# SCH_Aansluitschema_Jao_2023-12-15.net
KiCad netlist of a schematic drawn in EasyEDA
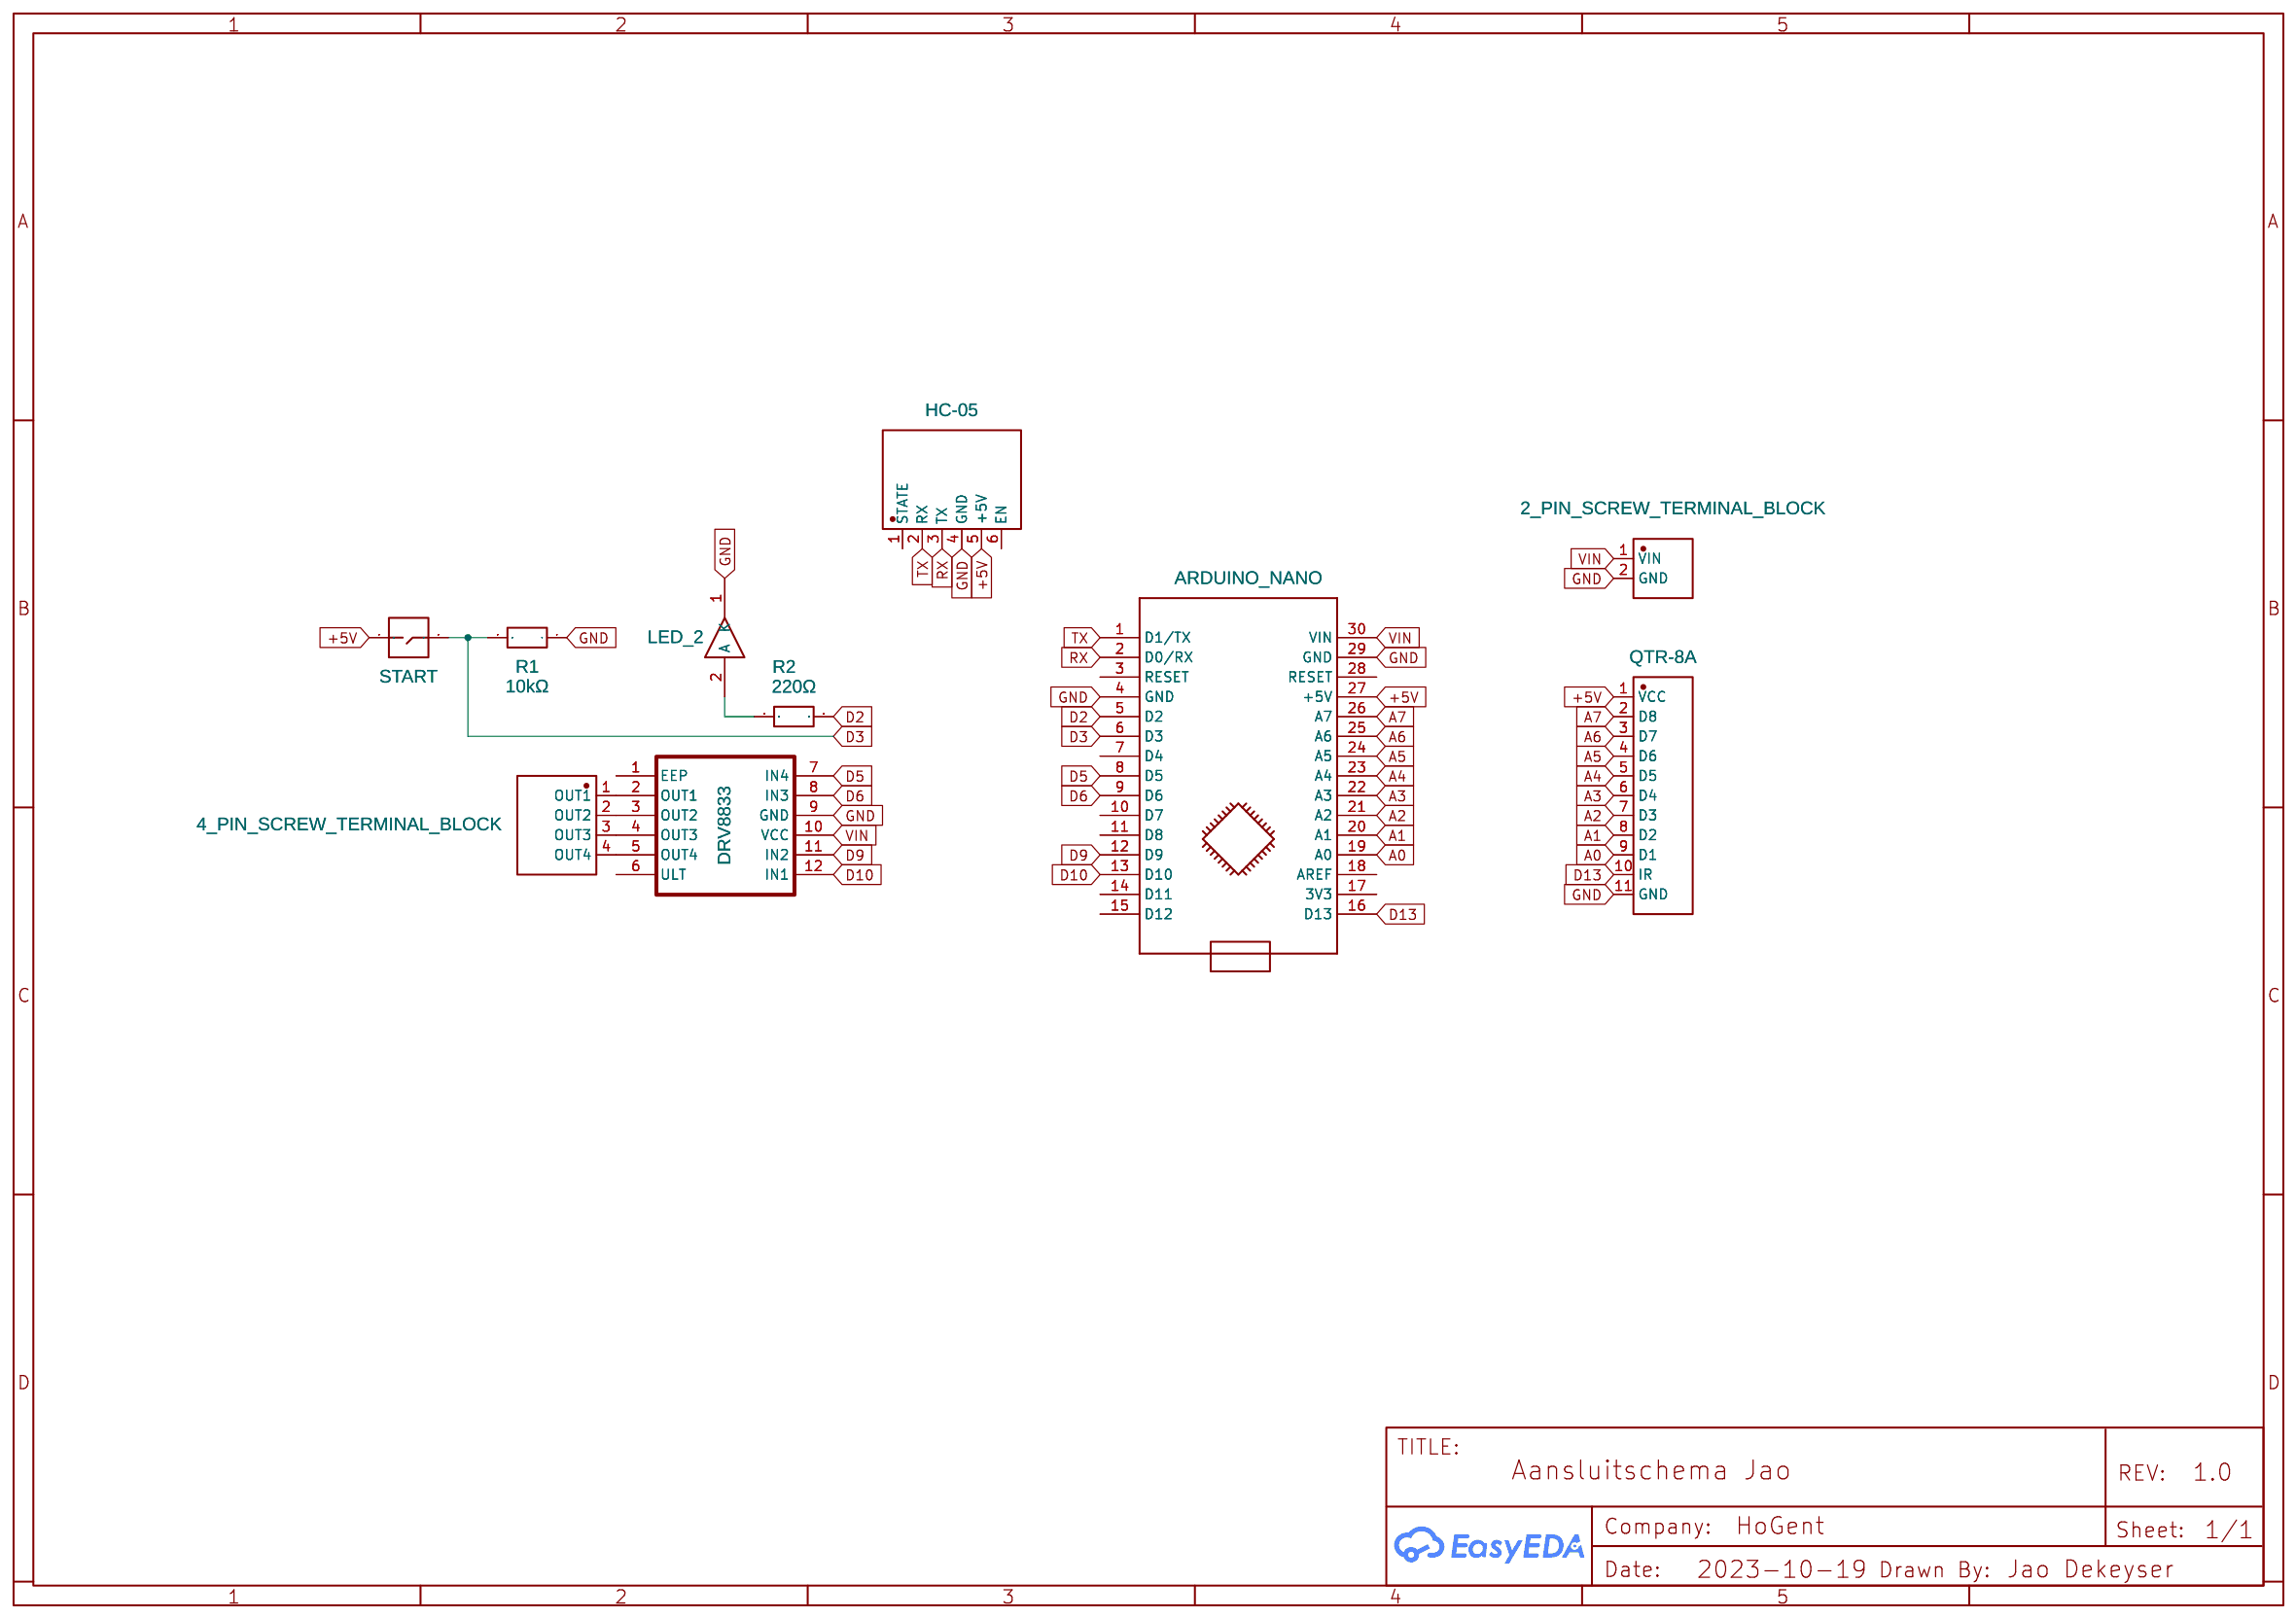
[diagram p0: schematic sheet]

(export (version "E")
  (design (tool "Eeschema 10.0.6"))
  (components
    (comp (ref "2_PIN_SCREW_TERMINAL_BLOCK")
      (value "2 Pin Screw Terminal Block Connector 2.54 mm")
      (libsource (lib "") (part "2 PIN SCREW TERMINAL BLOCK CONNECTOR 2.54 MM"))
    )
    (comp (ref "4_PIN_SCREW_TERMINAL_BLOCK")
      (value "4 PIN SCREW TERMINAL BLOCK CONNECTOR 2.54 MM")
      (libsource (lib "") (part "4 PIN SCREW TERMINAL BLOCK CONNECTOR 2.54 MM"))
    )
    (comp (ref "ARDUINO_NANO")
      (value "ARDUINO NANO CLOCK")
      (fields (field (name "Manufacturer Part") "Arduino-NANO"))
      (libsource (lib "") (part "ARDUINO NANO CLOCK"))
    )
    (comp (ref "DRV8833") (value "DRV8833") (libsource (lib "") (part "DRV8833 12PIN")))
    (comp (ref "HC-05") (value "HC-05") (libsource (lib "") (part "HC-05")))
    (comp (ref "LED_2") (value "led 5 mm") (libsource (lib "") (part "led 5 mm")))
    (comp (ref "QTR-8A") (value "QTR-8A") (libsource (lib "") (part "QTR-8A")))
    (comp (ref "R1")
      (value "10kΩ")
      (libsource (lib "") (part "AXIAL RESISTOR 220 OHM - TH_BD2.3-L6.0-P10.00-D0.4"))
    )
    (comp (ref "R2")
      (value "220Ω")
      (libsource (lib "") (part "AXIAL RESISTOR 220 OHM - TH_BD2.3-L6.0-P10.00-D0.4_1"))
    )
    (comp (ref "START") (value "start") (libsource (lib "") (part "Push Button")))
  )
  (nets
    (net (code "1") (name "+5V") (class "Default")
      (node (ref "ARDUINO_NANO") (pin "27") (pinfunction "+5V_27") (pintype "unspecified"))
      (node (ref "HC-05") (pin "5") (pinfunction "+5V_5") (pintype "unspecified"))
      (node (ref "QTR-8A") (pin "1") (pinfunction "VCC_1") (pintype "unspecified"))
      (node (ref "START") (pin "1") (pinfunction "1_1") (pintype "unspecified"))
    )
    (net (code "2") (name "A0") (class "Default")
      (node (ref "ARDUINO_NANO") (pin "19") (pinfunction "A0_19") (pintype "unspecified"))
      (node (ref "QTR-8A") (pin "9") (pinfunction "D1_9") (pintype "unspecified"))
    )
    (net (code "3") (name "A1") (class "Default")
      (node (ref "ARDUINO_NANO") (pin "20") (pinfunction "A1_20") (pintype "unspecified"))
      (node (ref "QTR-8A") (pin "8") (pinfunction "D2_8") (pintype "unspecified"))
    )
    (net (code "4") (name "A2") (class "Default")
      (node (ref "ARDUINO_NANO") (pin "21") (pinfunction "A2_21") (pintype "unspecified"))
      (node (ref "QTR-8A") (pin "7") (pinfunction "D3_7") (pintype "unspecified"))
    )
    (net (code "5") (name "A3") (class "Default")
      (node (ref "ARDUINO_NANO") (pin "22") (pinfunction "A3_22") (pintype "unspecified"))
      (node (ref "QTR-8A") (pin "6") (pinfunction "D4_6") (pintype "unspecified"))
    )
    (net (code "6") (name "A4") (class "Default")
      (node (ref "ARDUINO_NANO") (pin "23") (pinfunction "A4_23") (pintype "unspecified"))
      (node (ref "QTR-8A") (pin "5") (pinfunction "D5_5") (pintype "unspecified"))
    )
    (net (code "7") (name "A5") (class "Default")
      (node (ref "ARDUINO_NANO") (pin "24") (pinfunction "A5_24") (pintype "unspecified"))
      (node (ref "QTR-8A") (pin "4") (pinfunction "D6_4") (pintype "unspecified"))
    )
    (net (code "8") (name "A6") (class "Default")
      (node (ref "ARDUINO_NANO") (pin "25") (pinfunction "A6_25") (pintype "unspecified"))
      (node (ref "QTR-8A") (pin "3") (pinfunction "D7_3") (pintype "unspecified"))
    )
    (net (code "9") (name "A7") (class "Default")
      (node (ref "ARDUINO_NANO") (pin "26") (pinfunction "A7_26") (pintype "unspecified"))
      (node (ref "QTR-8A") (pin "2") (pinfunction "D8_2") (pintype "unspecified"))
    )
    (net (code "10") (name "D2") (class "Default")
      (node (ref "ARDUINO_NANO") (pin "5") (pinfunction "D2_5") (pintype "unspecified"))
      (node (ref "R2") (pin "2") (pinfunction "2_2") (pintype "unspecified"))
    )
    (net (code "11") (name "D3") (class "Default")
      (node (ref "ARDUINO_NANO") (pin "6") (pinfunction "D3_6") (pintype "unspecified"))
      (node (ref "R1") (pin "2") (pinfunction "2_2") (pintype "unspecified"))
      (node (ref "START") (pin "2") (pinfunction "2_2") (pintype "unspecified"))
    )
    (net (code "12") (name "D5") (class "Default")
      (node (ref "ARDUINO_NANO") (pin "8") (pinfunction "D5_8") (pintype "unspecified"))
      (node (ref "DRV8833") (pin "7") (pinfunction "IN4_7") (pintype "unspecified"))
    )
    (net (code "13") (name "D6") (class "Default")
      (node (ref "ARDUINO_NANO") (pin "9") (pinfunction "D6_9") (pintype "unspecified"))
      (node (ref "DRV8833") (pin "8") (pinfunction "IN3_8") (pintype "unspecified"))
    )
    (net (code "14") (name "D9") (class "Default")
      (node (ref "ARDUINO_NANO") (pin "12") (pinfunction "D9_12") (pintype "unspecified"))
      (node (ref "DRV8833") (pin "11") (pinfunction "IN2_11") (pintype "unspecified"))
    )
    (net (code "15") (name "D10") (class "Default")
      (node (ref "ARDUINO_NANO") (pin "13") (pinfunction "D10_13") (pintype "unspecified"))
      (node (ref "DRV8833") (pin "12") (pinfunction "IN1_12") (pintype "unspecified"))
    )
    (net (code "16") (name "D13") (class "Default")
      (node (ref "ARDUINO_NANO") (pin "16") (pinfunction "D13_16") (pintype "unspecified"))
      (node (ref "QTR-8A") (pin "10") (pinfunction "IR_10") (pintype "unspecified"))
    )
    (net (code "17") (name "GND") (class "Default")
      (node (ref "2_PIN_SCREW_TERMINAL_BLOCK") (pin "2") (pinfunction "GND_2") (pintype "unspecified"))
      (node (ref "ARDUINO_NANO") (pin "29") (pinfunction "GND_29") (pintype "unspecified"))
      (node (ref "ARDUINO_NANO") (pin "4") (pinfunction "GND_4") (pintype "unspecified"))
      (node (ref "DRV8833") (pin "9") (pinfunction "GND_9") (pintype "unspecified"))
      (node (ref "HC-05") (pin "4") (pinfunction "GND_4") (pintype "unspecified"))
      (node (ref "LED_2") (pin "1") (pinfunction "K_1") (pintype "unspecified"))
      (node (ref "QTR-8A") (pin "11") (pinfunction "GND_11") (pintype "unspecified"))
      (node (ref "R1") (pin "1") (pinfunction "1_1") (pintype "unspecified"))
    )
    (net (code "18") (name "Net-(4_PIN_SCREW_TERMINAL_BLOCK-OUT1)") (class "Default")
      (node (ref "4_PIN_SCREW_TERMINAL_BLOCK") (pin "1") (pinfunction "OUT1_1") (pintype "unspecified"))
      (node (ref "DRV8833") (pin "2") (pinfunction "OUT1_2") (pintype "unspecified"))
    )
    (net (code "19") (name "Net-(4_PIN_SCREW_TERMINAL_BLOCK-OUT2)") (class "Default")
      (node (ref "4_PIN_SCREW_TERMINAL_BLOCK") (pin "2") (pinfunction "OUT2_2") (pintype "unspecified"))
      (node (ref "DRV8833") (pin "3") (pinfunction "OUT2_3") (pintype "unspecified"))
    )
    (net (code "20") (name "Net-(4_PIN_SCREW_TERMINAL_BLOCK-OUT3)") (class "Default")
      (node (ref "4_PIN_SCREW_TERMINAL_BLOCK") (pin "3") (pinfunction "OUT3_3") (pintype "unspecified"))
      (node (ref "DRV8833") (pin "4") (pinfunction "OUT3_4") (pintype "unspecified"))
    )
    (net (code "21") (name "Net-(4_PIN_SCREW_TERMINAL_BLOCK-OUT4)") (class "Default")
      (node (ref "4_PIN_SCREW_TERMINAL_BLOCK") (pin "4") (pinfunction "OUT4_4") (pintype "unspecified"))
      (node (ref "DRV8833") (pin "5") (pinfunction "OUT4_5") (pintype "unspecified"))
    )
    (net (code "22") (name "Net-(LED_2-A)") (class "Default")
      (node (ref "LED_2") (pin "2") (pinfunction "A_2") (pintype "unspecified"))
      (node (ref "R2") (pin "1") (pinfunction "1_1") (pintype "unspecified"))
    )
    (net (code "23") (name "RX") (class "Default")
      (node (ref "ARDUINO_NANO") (pin "2") (pinfunction "D0/RX_2") (pintype "unspecified"))
      (node (ref "HC-05") (pin "3") (pinfunction "TX_3") (pintype "unspecified"))
    )
    (net (code "24") (name "TX") (class "Default")
      (node (ref "ARDUINO_NANO") (pin "1") (pinfunction "D1/TX_1") (pintype "unspecified"))
      (node (ref "HC-05") (pin "2") (pinfunction "RX_2") (pintype "unspecified"))
    )
    (net (code "25") (name "VIN") (class "Default")
      (node (ref "2_PIN_SCREW_TERMINAL_BLOCK") (pin "1") (pinfunction "VIN_1") (pintype "unspecified"))
      (node (ref "ARDUINO_NANO") (pin "30") (pinfunction "VIN_30") (pintype "unspecified"))
      (node (ref "DRV8833") (pin "10") (pinfunction "VCC_10") (pintype "unspecified"))
    )
    (net (code "26") (name "unconnected-(ARDUINO_NANO-3V3-Pad17)") (class "Default")
      (node (ref "ARDUINO_NANO") (pin "17") (pinfunction "3V3_17") (pintype "unspecified"))
    )
    (net (code "27") (name "unconnected-(ARDUINO_NANO-AREF-Pad18)") (class "Default")
      (node (ref "ARDUINO_NANO") (pin "18") (pinfunction "AREF_18") (pintype "unspecified"))
    )
    (net (code "28") (name "unconnected-(ARDUINO_NANO-D4-Pad7)") (class "Default")
      (node (ref "ARDUINO_NANO") (pin "7") (pinfunction "D4_7") (pintype "unspecified"))
    )
    (net (code "29") (name "unconnected-(ARDUINO_NANO-D7-Pad10)") (class "Default")
      (node (ref "ARDUINO_NANO") (pin "10") (pinfunction "D7_10") (pintype "unspecified"))
    )
    (net (code "30") (name "unconnected-(ARDUINO_NANO-D8-Pad11)") (class "Default")
      (node (ref "ARDUINO_NANO") (pin "11") (pinfunction "D8_11") (pintype "unspecified"))
    )
    (net (code "31") (name "unconnected-(ARDUINO_NANO-D11-Pad14)") (class "Default")
      (node (ref "ARDUINO_NANO") (pin "14") (pinfunction "D11_14") (pintype "unspecified"))
    )
    (net (code "32") (name "unconnected-(ARDUINO_NANO-D12-Pad15)") (class "Default")
      (node (ref "ARDUINO_NANO") (pin "15") (pinfunction "D12_15") (pintype "unspecified"))
    )
    (net (code "33") (name "unconnected-(ARDUINO_NANO-RESET-Pad3)") (class "Default")
      (node (ref "ARDUINO_NANO") (pin "3") (pinfunction "RESET_3") (pintype "unspecified"))
    )
    (net (code "34") (name "unconnected-(ARDUINO_NANO-RESET-Pad28)") (class "Default")
      (node (ref "ARDUINO_NANO") (pin "28") (pinfunction "RESET_28") (pintype "unspecified"))
    )
    (net (code "35") (name "unconnected-(DRV8833-EEP-Pad1)") (class "Default")
      (node (ref "DRV8833") (pin "1") (pinfunction "EEP_1") (pintype "unspecified"))
    )
    (net (code "36") (name "unconnected-(DRV8833-ULT-Pad6)") (class "Default")
      (node (ref "DRV8833") (pin "6") (pinfunction "ULT_6") (pintype "unspecified"))
    )
    (net (code "37") (name "unconnected-(HC-05-EN-Pad6)") (class "Default")
      (node (ref "HC-05") (pin "6") (pinfunction "EN_6") (pintype "unspecified"))
    )
    (net (code "38") (name "unconnected-(HC-05-STATE-Pad1)") (class "Default")
      (node (ref "HC-05") (pin "1") (pinfunction "STATE_1") (pintype "unspecified"))
    )
  )
)
